# ms_kb_reader.net
KiCad netlist of a schematic drawn in EAGLE
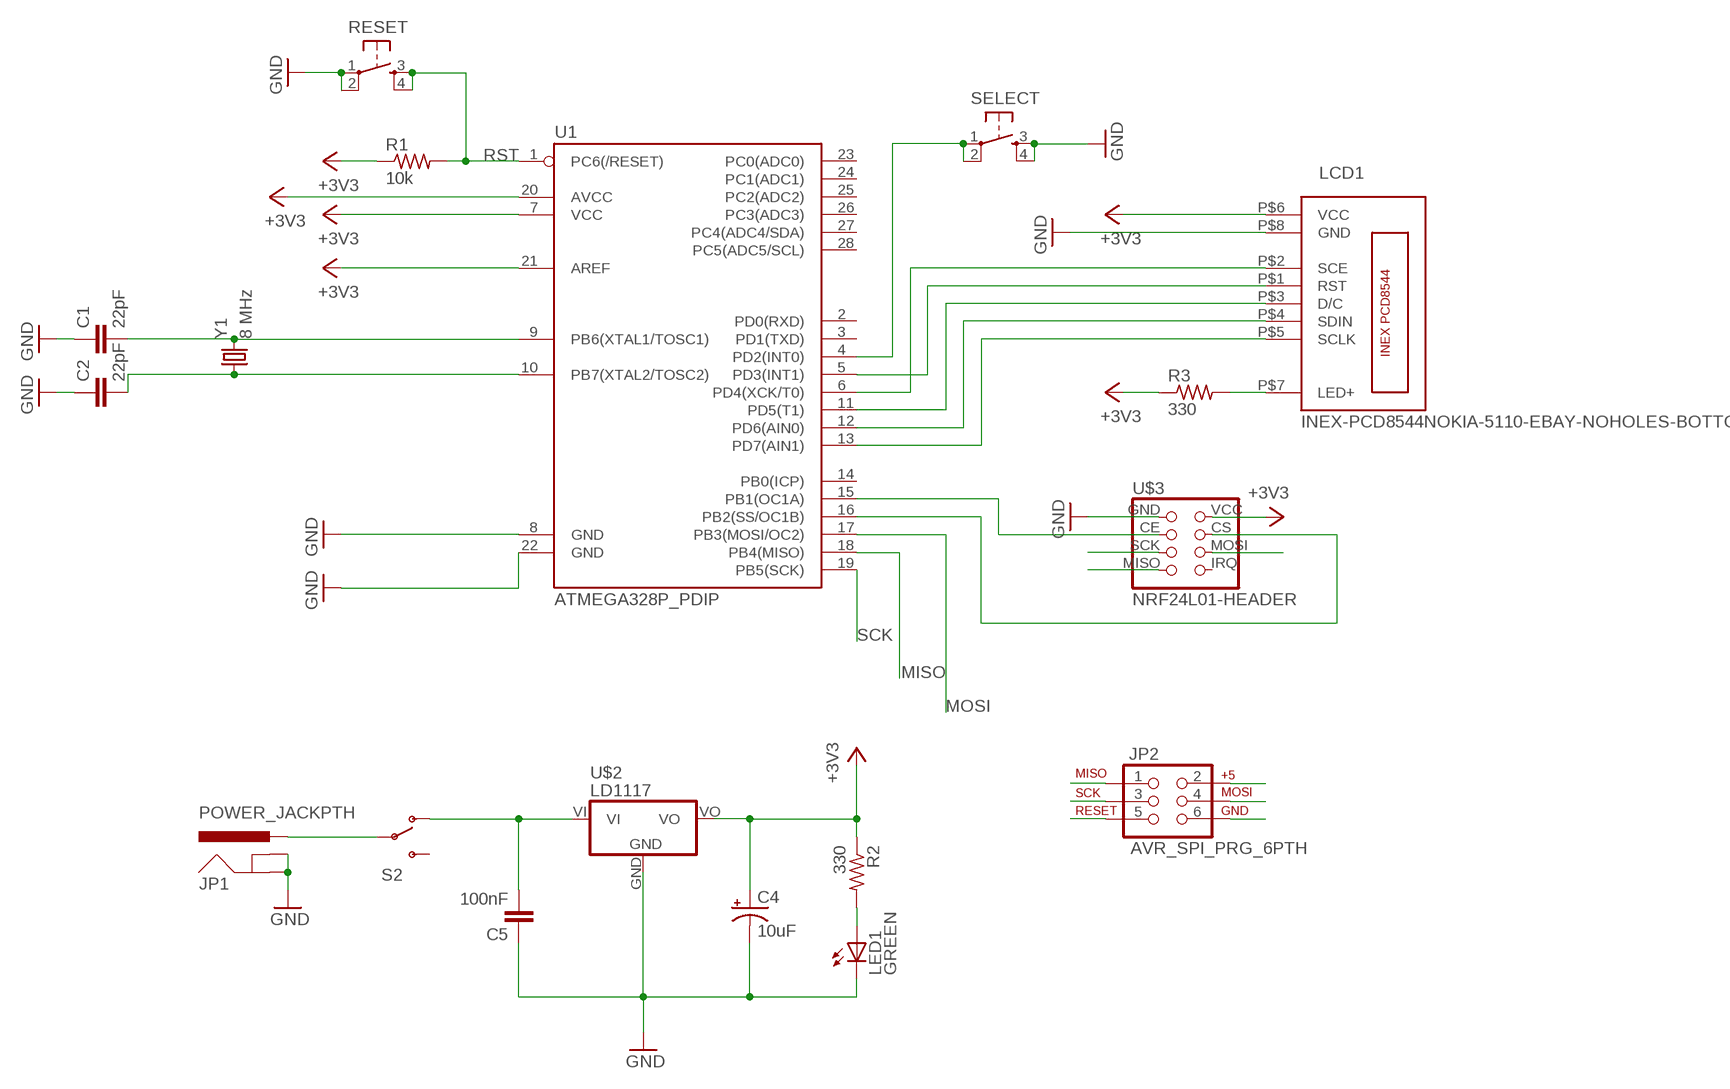
[diagram p0: schematic, sheet 1]

(export (version "E")
  (design (tool "Eeschema 10.0.6"))
  (components
    (comp (ref "C1")
      (value "22pF")
      (footprint "eagle-import:CAP-PTH-SMALL")
      (libsource (lib "eagle-import") (part "CAPPTH"))
    )
    (comp (ref "C2")
      (value "22pF")
      (footprint "eagle-import:CAP-PTH-SMALL")
      (libsource (lib "eagle-import") (part "CAPPTH"))
    )
    (comp (ref "C4")
      (value "10uF")
      (footprint "eagle-import:E2,5-5")
      (libsource (lib "eagle-import") (part "CPOL-USE2.5-5"))
    )
    (comp (ref "C5")
      (value "100nF")
      (footprint "eagle-import:CAP-PTH-SMALL")
      (libsource (lib "eagle-import") (part "CAPPTH"))
    )
    (comp (ref "JP1")
      (value "POWER_JACKPTH")
      (footprint "eagle-import:POWER_JACK_PTH")
      (libsource (lib "eagle-import") (part "POWER_JACKPTH"))
    )
    (comp (ref "JP2")
      (value "AVR_SPI_PRG_6PTH")
      (footprint "eagle-import:2X3")
      (libsource (lib "eagle-import") (part "AVR_SPI_PRG_6PTH"))
    )
    (comp (ref "LCD1")
      (value "INEX-PCD8544NOKIA-5110-EBAY-NOHOLES-BOTTOM")
      (footprint "eagle-import:NOKIA-5110-EBAY-NOHOLES")
      (libsource (lib "eagle-import") (part "INEX-PCD8544NOKIA-5110-EBAY-NOHOLES-BOTTOM"))
    )
    (comp (ref "LED1")
      (value "GREEN")
      (footprint "eagle-import:LED5MM")
      (libsource (lib "eagle-import") (part "LED5MM"))
    )
    (comp (ref "R1")
      (value "10k")
      (footprint "eagle-import:0207_10")
      (libsource (lib "eagle-import") (part "R-US_0207/10"))
    )
    (comp (ref "R2")
      (value "330")
      (footprint "eagle-import:0207_10")
      (libsource (lib "eagle-import") (part "R-US_0207/10"))
    )
    (comp (ref "R3")
      (value "330")
      (footprint "eagle-import:0207_10")
      (libsource (lib "eagle-import") (part "R-US_0207/10"))
    )
    (comp (ref "RESET")
      (value "TACTILE-SWITCH-PTH")
      (footprint "eagle-import:TAC-SWITCH-PTH")
      (libsource (lib "eagle-import") (part "TACTILE-SWITCH-PTH"))
    )
    (comp (ref "S2")
      (value "SWITCH-SPDTPTH_LOCK")
      (footprint "eagle-import:SWITCH-SPDT_LOCK.007S")
      (libsource (lib "eagle-import") (part "SWITCH-SPDTPTH_LOCK"))
    )
    (comp (ref "SELECT")
      (value "TACTILE-SWITCH-PTH")
      (footprint "eagle-import:TAC-SWITCH-PTH")
      (libsource (lib "eagle-import") (part "TACTILE-SWITCH-PTH"))
    )
    (comp (ref "U$2")
      (value "LD1117")
      (footprint "eagle-import:LD1117")
      (libsource (lib "eagle-import") (part "LD1117"))
    )
    (comp (ref "U$3")
      (value "NRF24L01-HEADER")
      (footprint "eagle-import:NRF24L01-HEADER")
      (libsource (lib "eagle-import") (part "NRF24L01-HEADER"))
    )
    (comp (ref "U1")
      (value "ATMEGA328P_PDIP")
      (footprint "eagle-import:DIL28-3")
      (libsource (lib "eagle-import") (part "ATMEGA328P_PDIP"))
    )
    (comp (ref "Y1")
      (value "8 MHz")
      (footprint "eagle-import:HC49US")
      (libsource (lib "eagle-import") (part "CRYSTALHC49US"))
    )
  )
  (nets
    (net (code "1") (name "+3V3") (class "Default")
      (node (ref "C4") (pin "+") (pinfunction "+_+") (pintype "passive"))
      (node (ref "JP2") (pin "2") (pinfunction "2_2") (pintype "passive"))
      (node (ref "LCD1") (pin "P$6") (pinfunction "VCC_P$6") (pintype "power_in"))
      (node (ref "R1") (pin "1") (pinfunction "1_1") (pintype "passive"))
      (node (ref "R2") (pin "1") (pinfunction "1_1") (pintype "passive"))
      (node (ref "R3") (pin "1") (pinfunction "1_1") (pintype "passive"))
      (node (ref "U$2") (pin "VO") (pinfunction "VO_VO") (pintype "passive"))
      (node (ref "U$3") (pin "VCC") (pinfunction "VCC_VCC") (pintype "passive"))
      (node (ref "U1") (pin "20") (pinfunction "AVCC_20") (pintype "bidirectional"))
      (node (ref "U1") (pin "21") (pinfunction "AREF_21") (pintype "bidirectional"))
      (node (ref "U1") (pin "7") (pinfunction "VCC_7") (pintype "bidirectional"))
    )
    (net (code "2") (name "/MISO") (class "Default")
      (node (ref "JP2") (pin "1") (pinfunction "1_1") (pintype "passive"))
      (node (ref "U$3") (pin "MISO") (pinfunction "MISO_MISO") (pintype "passive"))
      (node (ref "U1") (pin "18") (pinfunction "PB4(MISO)_18") (pintype "bidirectional"))
    )
    (net (code "3") (name "/MOSI") (class "Default")
      (node (ref "JP2") (pin "4") (pinfunction "4_4") (pintype "passive"))
      (node (ref "U$3") (pin "MOSI") (pinfunction "MOSI_MOSI") (pintype "passive"))
      (node (ref "U1") (pin "17") (pinfunction "PB3(MOSI/OC2)_17") (pintype "bidirectional"))
    )
    (net (code "4") (name "/RST") (class "Default")
      (node (ref "JP2") (pin "5") (pinfunction "5_5") (pintype "passive"))
      (node (ref "R1") (pin "2") (pinfunction "2_2") (pintype "passive"))
      (node (ref "RESET") (pin "3") (pinfunction "3_3") (pintype "passive"))
      (node (ref "RESET") (pin "4") (pinfunction "4_4") (pintype "passive"))
      (node (ref "U1") (pin "1") (pinfunction "PC6(/RESET)_1") (pintype "bidirectional"))
    )
    (net (code "5") (name "/SCK") (class "Default")
      (node (ref "JP2") (pin "3") (pinfunction "3_3") (pintype "passive"))
      (node (ref "U$3") (pin "SCK") (pinfunction "SCK_SCK") (pintype "passive"))
      (node (ref "U1") (pin "19") (pinfunction "PB5(SCK)_19") (pintype "bidirectional"))
    )
    (net (code "6") (name "GND") (class "Default")
      (node (ref "C1") (pin "1") (pinfunction "1_1") (pintype "passive"))
      (node (ref "C2") (pin "1") (pinfunction "1_1") (pintype "passive"))
      (node (ref "C4") (pin "-") (pinfunction "-_-") (pintype "passive"))
      (node (ref "C5") (pin "1") (pinfunction "1_1") (pintype "passive"))
      (node (ref "JP1") (pin "GND") (pinfunction "GND_GND") (pintype "bidirectional"))
      (node (ref "JP1") (pin "GNDBREAK") (pinfunction "GNDBREAK_GNDBREAK") (pintype "bidirectional"))
      (node (ref "JP2") (pin "6") (pinfunction "6_6") (pintype "passive"))
      (node (ref "LCD1") (pin "P$8") (pinfunction "GND_P$8") (pintype "power_in"))
      (node (ref "LED1") (pin "K") (pinfunction "C_K") (pintype "passive"))
      (node (ref "RESET") (pin "1") (pinfunction "1_1") (pintype "passive"))
      (node (ref "RESET") (pin "2") (pinfunction "2_2") (pintype "passive"))
      (node (ref "SELECT") (pin "3") (pinfunction "3_3") (pintype "passive"))
      (node (ref "SELECT") (pin "4") (pinfunction "4_4") (pintype "passive"))
      (node (ref "U$2") (pin "GND") (pinfunction "GND_GND") (pintype "passive"))
      (node (ref "U$3") (pin "GND") (pinfunction "GND_GND") (pintype "passive"))
      (node (ref "U1") (pin "22") (pinfunction "GND_22") (pintype "bidirectional"))
      (node (ref "U1") (pin "8") (pinfunction "GND_8") (pintype "bidirectional"))
    )
    (net (code "7") (name "Net-(LCD1-D{slash}C)") (class "Default")
      (node (ref "LCD1") (pin "P$3") (pinfunction "D/C_P$3") (pintype "input"))
      (node (ref "U1") (pin "11") (pinfunction "PD5(T1)_11") (pintype "bidirectional"))
    )
    (net (code "8") (name "Net-(LCD1-LED+)") (class "Default")
      (node (ref "LCD1") (pin "P$7") (pinfunction "LED+_P$7") (pintype "power_in"))
      (node (ref "R3") (pin "2") (pinfunction "2_2") (pintype "passive"))
    )
    (net (code "9") (name "Net-(LCD1-RST)") (class "Default")
      (node (ref "LCD1") (pin "P$1") (pinfunction "RST_P$1") (pintype "input"))
      (node (ref "U1") (pin "5") (pinfunction "PD3(INT1)_5") (pintype "bidirectional"))
    )
    (net (code "10") (name "Net-(LCD1-SCE)") (class "Default")
      (node (ref "LCD1") (pin "P$2") (pinfunction "SCE_P$2") (pintype "input"))
      (node (ref "U1") (pin "6") (pinfunction "PD4(XCK/T0)_6") (pintype "bidirectional"))
    )
    (net (code "11") (name "Net-(LCD1-SCLK)") (class "Default")
      (node (ref "LCD1") (pin "P$5") (pinfunction "SCLK_P$5") (pintype "input"))
      (node (ref "U1") (pin "13") (pinfunction "PD7(AIN1)_13") (pintype "bidirectional"))
    )
    (net (code "12") (name "Net-(LCD1-SDIN)") (class "Default")
      (node (ref "LCD1") (pin "P$4") (pinfunction "SDIN_P$4") (pintype "input"))
      (node (ref "U1") (pin "12") (pinfunction "PD6(AIN0)_12") (pintype "bidirectional"))
    )
    (net (code "13") (name "Net-(LED1-PadA)") (class "Default")
      (node (ref "LED1") (pin "A") (pinfunction "A_A") (pintype "passive"))
      (node (ref "R2") (pin "2") (pinfunction "2_2") (pintype "passive"))
    )
    (net (code "14") (name "Net-(S2-O)") (class "Default")
      (node (ref "C5") (pin "2") (pinfunction "2_2") (pintype "passive"))
      (node (ref "S2") (pin "1") (pinfunction "O_1") (pintype "passive"))
      (node (ref "U$2") (pin "VI") (pinfunction "VI_VI") (pintype "input"))
    )
    (net (code "15") (name "Net-(S2-P)") (class "Default")
      (node (ref "JP1") (pin "PWR") (pinfunction "PWR_PWR") (pintype "bidirectional"))
      (node (ref "S2") (pin "2") (pinfunction "P_2") (pintype "passive"))
    )
    (net (code "16") (name "Net-(U1-PB1(OC1A))") (class "Default")
      (node (ref "U$3") (pin "CE") (pinfunction "CE_CE") (pintype "passive"))
      (node (ref "U1") (pin "15") (pinfunction "PB1(OC1A)_15") (pintype "bidirectional"))
    )
    (net (code "17") (name "Net-(U1-PB2(SS{slash}OC1B))") (class "Default")
      (node (ref "U$3") (pin "CS") (pinfunction "CS_CS") (pintype "passive"))
      (node (ref "U1") (pin "16") (pinfunction "PB2(SS/OC1B)_16") (pintype "bidirectional"))
    )
    (net (code "18") (name "Net-(U1-PB6(XTAL1{slash}TOSC1))") (class "Default")
      (node (ref "C1") (pin "2") (pinfunction "2_2") (pintype "passive"))
      (node (ref "U1") (pin "9") (pinfunction "PB6(XTAL1/TOSC1)_9") (pintype "bidirectional"))
      (node (ref "Y1") (pin "2") (pinfunction "2_2") (pintype "passive"))
    )
    (net (code "19") (name "Net-(U1-PB7(XTAL2{slash}TOSC2))") (class "Default")
      (node (ref "C2") (pin "2") (pinfunction "2_2") (pintype "passive"))
      (node (ref "U1") (pin "10") (pinfunction "PB7(XTAL2/TOSC2)_10") (pintype "bidirectional"))
      (node (ref "Y1") (pin "1") (pinfunction "1_1") (pintype "passive"))
    )
    (net (code "20") (name "Net-(U1-PD2(INT0))") (class "Default")
      (node (ref "SELECT") (pin "1") (pinfunction "1_1") (pintype "passive"))
      (node (ref "SELECT") (pin "2") (pinfunction "2_2") (pintype "passive"))
      (node (ref "U1") (pin "4") (pinfunction "PD2(INT0)_4") (pintype "bidirectional"))
    )
    (net (code "21") (name "unconnected-(S2-S-Pad3)") (class "Default")
      (node (ref "S2") (pin "3") (pinfunction "S_3") (pintype "passive"))
    )
    (net (code "22") (name "unconnected-(U$3-PadIRQ)") (class "Default")
      (node (ref "U$3") (pin "IRQ") (pinfunction "IRQ_IRQ") (pintype "passive"))
    )
    (net (code "23") (name "unconnected-(U1-PB0(ICP)-Pad14)") (class "Default")
      (node (ref "U1") (pin "14") (pinfunction "PB0(ICP)_14") (pintype "bidirectional"))
    )
    (net (code "24") (name "unconnected-(U1-PC0(ADC0)-Pad23)") (class "Default")
      (node (ref "U1") (pin "23") (pinfunction "PC0(ADC0)_23") (pintype "bidirectional"))
    )
    (net (code "25") (name "unconnected-(U1-PC1(ADC1)-Pad24)") (class "Default")
      (node (ref "U1") (pin "24") (pinfunction "PC1(ADC1)_24") (pintype "bidirectional"))
    )
    (net (code "26") (name "unconnected-(U1-PC2(ADC2)-Pad25)") (class "Default")
      (node (ref "U1") (pin "25") (pinfunction "PC2(ADC2)_25") (pintype "bidirectional"))
    )
    (net (code "27") (name "unconnected-(U1-PC3(ADC3)-Pad26)") (class "Default")
      (node (ref "U1") (pin "26") (pinfunction "PC3(ADC3)_26") (pintype "bidirectional"))
    )
    (net (code "28") (name "unconnected-(U1-PC4(ADC4{slash}SDA)-Pad27)") (class "Default")
      (node (ref "U1") (pin "27") (pinfunction "PC4(ADC4/SDA)_27") (pintype "bidirectional"))
    )
    (net (code "29") (name "unconnected-(U1-PC5(ADC5{slash}SCL)-Pad28)") (class "Default")
      (node (ref "U1") (pin "28") (pinfunction "PC5(ADC5/SCL)_28") (pintype "bidirectional"))
    )
    (net (code "30") (name "unconnected-(U1-PD0(RXD)-Pad2)") (class "Default")
      (node (ref "U1") (pin "2") (pinfunction "PD0(RXD)_2") (pintype "bidirectional"))
    )
    (net (code "31") (name "unconnected-(U1-PD1(TXD)-Pad3)") (class "Default")
      (node (ref "U1") (pin "3") (pinfunction "PD1(TXD)_3") (pintype "bidirectional"))
    )
  )
)
